# magnilamp_led_driver.net
KiCad netlist of a schematic drawn in EAGLE
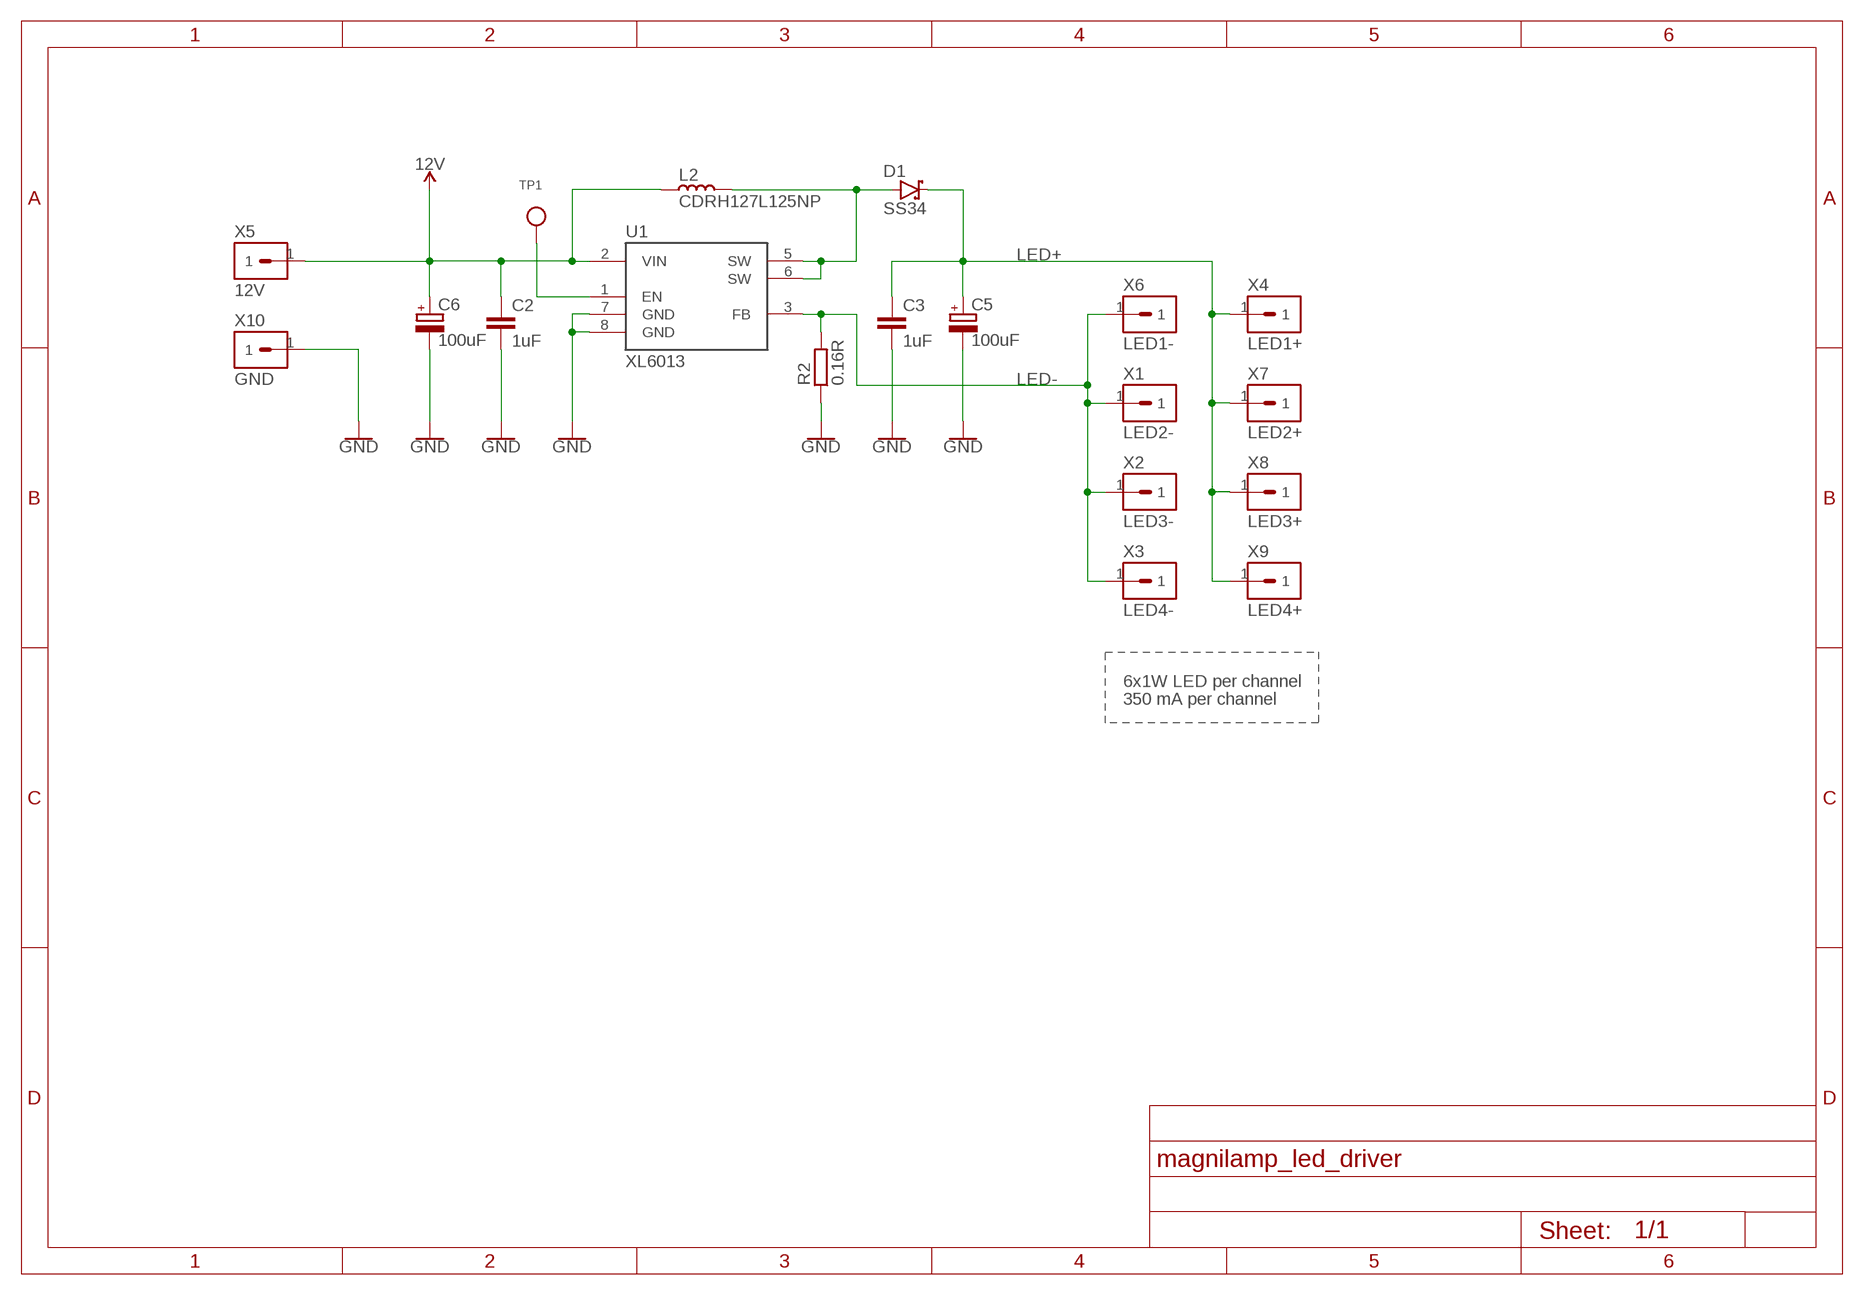
[diagram p0: schematic, sheet 1]

(export (version "E")
  (design (tool "Eeschema 10.0.6"))
  (components
    (comp (ref "C2")
      (value "1uF")
      (footprint "eagle-import:C0603")
      (libsource (lib "eagle-import") (part "CAPC0603"))
    )
    (comp (ref "C3")
      (value "1uF")
      (footprint "eagle-import:C0603")
      (libsource (lib "eagle-import") (part "CAPC0603"))
    )
    (comp (ref "C5")
      (value "100uF")
      (footprint "eagle-import:KEMET-KN")
      (libsource (lib "eagle-import") (part "CAP-KEMETKN"))
    )
    (comp (ref "C6")
      (value "100uF")
      (footprint "eagle-import:KEMET-KN")
      (libsource (lib "eagle-import") (part "CAP-KEMETKN"))
    )
    (comp (ref "D1")
      (value "SS34")
      (footprint "eagle-import:DO-214AC")
      (libsource (lib "eagle-import") (part "DIODE-SCHOTTKYDO-214AC"))
    )
    (comp (ref "L2")
      (value "CDRH127L125NP")
      (footprint "eagle-import:SUMIDA-CDRH127L125")
      (libsource (lib "eagle-import") (part "IND-SUMIDACDRH127L125"))
    )
    (comp (ref "R2")
      (value "0.16R")
      (footprint "eagle-import:R1206")
      (libsource (lib "eagle-import") (part "RESISTOR1206"))
    )
    (comp (ref "TP1")
      (value "TESTPOINTPAD")
      (footprint "eagle-import:TESTPOINT_PAD_2MM")
      (libsource (lib "eagle-import") (part "TESTPOINTPAD"))
    )
    (comp (ref "U1")
      (value "XL6013")
      (footprint "eagle-import:SOP8")
      (libsource (lib "eagle-import") (part "XLSEMI-XL6013"))
    )
    (comp (ref "X1")
      (value "LED2-")
      (footprint "eagle-import:SOLDERPAD-4X5")
      (libsource (lib "eagle-import") (part "SOLDERPAD4X5"))
    )
    (comp (ref "X2")
      (value "LED3-")
      (footprint "eagle-import:SOLDERPAD-4X5")
      (libsource (lib "eagle-import") (part "SOLDERPAD4X5"))
    )
    (comp (ref "X3")
      (value "LED4-")
      (footprint "eagle-import:SOLDERPAD-4X5")
      (libsource (lib "eagle-import") (part "SOLDERPAD4X5"))
    )
    (comp (ref "X4")
      (value "LED1+")
      (footprint "eagle-import:SOLDERPAD-4X5")
      (libsource (lib "eagle-import") (part "SOLDERPAD4X5"))
    )
    (comp (ref "X5")
      (value "12V")
      (footprint "eagle-import:SOLDERPAD-4X5")
      (libsource (lib "eagle-import") (part "SOLDERPAD4X5"))
    )
    (comp (ref "X6")
      (value "LED1-")
      (footprint "eagle-import:SOLDERPAD-4X5")
      (libsource (lib "eagle-import") (part "SOLDERPAD4X5"))
    )
    (comp (ref "X7")
      (value "LED2+")
      (footprint "eagle-import:SOLDERPAD-4X5")
      (libsource (lib "eagle-import") (part "SOLDERPAD4X5"))
    )
    (comp (ref "X8")
      (value "LED3+")
      (footprint "eagle-import:SOLDERPAD-4X5")
      (libsource (lib "eagle-import") (part "SOLDERPAD4X5"))
    )
    (comp (ref "X9")
      (value "LED4+")
      (footprint "eagle-import:SOLDERPAD-4X5")
      (libsource (lib "eagle-import") (part "SOLDERPAD4X5"))
    )
    (comp (ref "X10")
      (value "GND")
      (footprint "eagle-import:SOLDERPAD-4X5")
      (libsource (lib "eagle-import") (part "SOLDERPAD4X5"))
    )
  )
  (nets
    (net (code "1") (name "/LED+") (class "Default")
      (node (ref "C3") (pin "1") (pinfunction "1_1") (pintype "passive"))
      (node (ref "C5") (pin "+") (pinfunction "+_+") (pintype "passive"))
      (node (ref "D1") (pin "C") (pinfunction "C_C") (pintype "passive"))
      (node (ref "X4") (pin "1") (pinfunction "1_1") (pintype "passive"))
      (node (ref "X7") (pin "1") (pinfunction "1_1") (pintype "passive"))
      (node (ref "X8") (pin "1") (pinfunction "1_1") (pintype "passive"))
      (node (ref "X9") (pin "1") (pinfunction "1_1") (pintype "passive"))
    )
    (net (code "2") (name "/LED-") (class "Default")
      (node (ref "R2") (pin "2") (pinfunction "2_2") (pintype "passive"))
      (node (ref "U1") (pin "3") (pinfunction "FB_3") (pintype "bidirectional"))
      (node (ref "X1") (pin "1") (pinfunction "1_1") (pintype "passive"))
      (node (ref "X2") (pin "1") (pinfunction "1_1") (pintype "passive"))
      (node (ref "X3") (pin "1") (pinfunction "1_1") (pintype "passive"))
      (node (ref "X6") (pin "1") (pinfunction "1_1") (pintype "passive"))
    )
    (net (code "3") (name "12V") (class "Default")
      (node (ref "C2") (pin "1") (pinfunction "1_1") (pintype "passive"))
      (node (ref "C6") (pin "+") (pinfunction "+_+") (pintype "passive"))
      (node (ref "L2") (pin "1") (pinfunction "1_1") (pintype "passive"))
      (node (ref "U1") (pin "2") (pinfunction "VIN_2") (pintype "bidirectional"))
      (node (ref "X5") (pin "1") (pinfunction "1_1") (pintype "passive"))
    )
    (net (code "4") (name "GND") (class "Default")
      (node (ref "C2") (pin "2") (pinfunction "2_2") (pintype "passive"))
      (node (ref "C3") (pin "2") (pinfunction "2_2") (pintype "passive"))
      (node (ref "C5") (pin "-") (pinfunction "-_-") (pintype "passive"))
      (node (ref "C6") (pin "-") (pinfunction "-_-") (pintype "passive"))
      (node (ref "R2") (pin "1") (pinfunction "1_1") (pintype "passive"))
      (node (ref "U1") (pin "7") (pinfunction "GND_7") (pintype "bidirectional"))
      (node (ref "U1") (pin "8") (pinfunction "GND_8") (pintype "bidirectional"))
      (node (ref "X10") (pin "1") (pinfunction "1_1") (pintype "passive"))
    )
    (net (code "5") (name "Net-(D1-PadA)") (class "Default")
      (node (ref "D1") (pin "A") (pinfunction "A_A") (pintype "passive"))
      (node (ref "L2") (pin "2") (pinfunction "2_2") (pintype "passive"))
      (node (ref "U1") (pin "5") (pinfunction "SW_5") (pintype "bidirectional"))
      (node (ref "U1") (pin "6") (pinfunction "SW_6") (pintype "bidirectional"))
    )
    (net (code "6") (name "Net-(U1-EN)") (class "Default")
      (node (ref "TP1") (pin "P$1") (pinfunction "P$1_P$1") (pintype "bidirectional"))
      (node (ref "U1") (pin "1") (pinfunction "EN_1") (pintype "bidirectional"))
    )
  )
)
